# converter.net
KiCad netlist of a schematic drawn in EAGLE
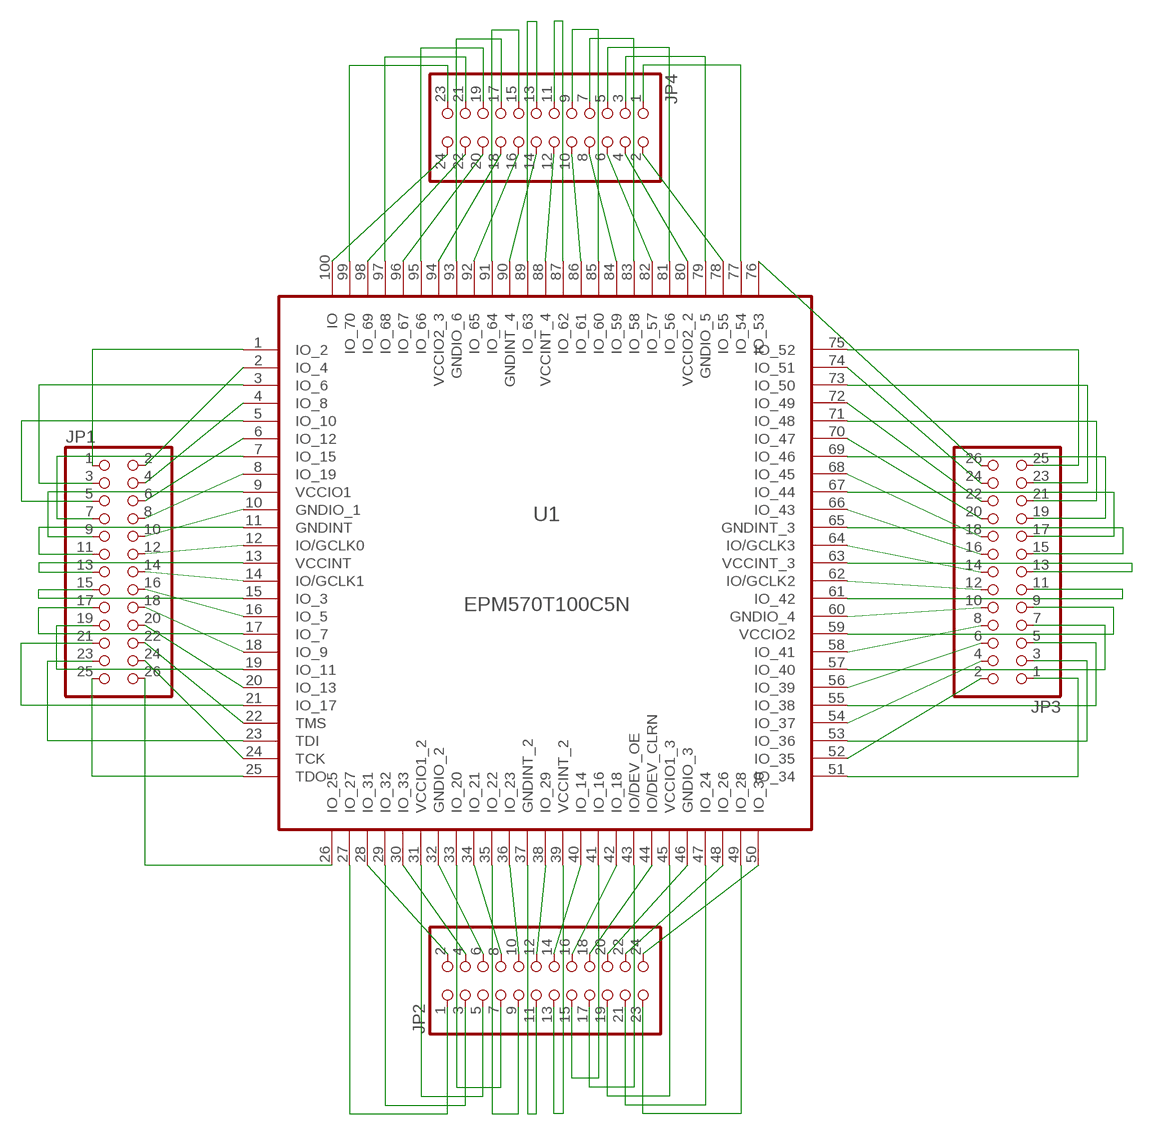
[diagram p0: schematic, sheet 1]

(export (version "E")
  (design (tool "Eeschema 10.0.6"))
  (components
    (comp (ref "JP1")
      (value "PINHD-2X13")
      (footprint "eagle-import:2X13")
      (libsource (lib "eagle-import") (part "PINHD-2X13"))
    )
    (comp (ref "JP2")
      (value "PINHD-2X12")
      (footprint "eagle-import:2X12")
      (libsource (lib "eagle-import") (part "PINHD-2X12"))
    )
    (comp (ref "JP3")
      (value "PINHD-2X13")
      (footprint "eagle-import:2X13")
      (libsource (lib "eagle-import") (part "PINHD-2X13"))
    )
    (comp (ref "JP4")
      (value "PINHD-2X12")
      (footprint "eagle-import:2X12")
      (libsource (lib "eagle-import") (part "PINHD-2X12"))
    )
    (comp (ref "U1")
      (value "EPM570T100C5N")
      (footprint "eagle-import:QFP50P1600X1600X120-100N")
      (libsource (lib "eagle-import") (part "SQUARE-QFP"))
    )
  )
  (nets
    (net (code "1") (name "Net-(U1-GNDINT)") (class "Default")
      (node (ref "JP1") (pin "11") (pinfunction "11_11") (pintype "passive"))
      (node (ref "U1") (pin "11") (pinfunction "GNDINT_11") (pintype "passive"))
    )
    (net (code "2") (name "Net-(U1-GNDINT_2)") (class "Default")
      (node (ref "JP2") (pin "11") (pinfunction "11_11") (pintype "passive"))
      (node (ref "U1") (pin "37") (pinfunction "GNDINT_2_37") (pintype "passive"))
    )
    (net (code "3") (name "Net-(U1-GNDINT_3)") (class "Default")
      (node (ref "JP3") (pin "15") (pinfunction "15_15") (pintype "passive"))
      (node (ref "U1") (pin "65") (pinfunction "GNDINT_3_65") (pintype "passive"))
    )
    (net (code "4") (name "Net-(U1-GNDINT_4)") (class "Default")
      (node (ref "JP4") (pin "14") (pinfunction "14_14") (pintype "passive"))
      (node (ref "U1") (pin "90") (pinfunction "GNDINT_4_90") (pintype "passive"))
    )
    (net (code "5") (name "Net-(U1-GNDIO_1)") (class "Default")
      (node (ref "JP1") (pin "10") (pinfunction "10_10") (pintype "passive"))
      (node (ref "U1") (pin "10") (pinfunction "GNDIO_1_10") (pintype "passive"))
    )
    (net (code "6") (name "Net-(U1-GNDIO_2)") (class "Default")
      (node (ref "JP2") (pin "6") (pinfunction "6_6") (pintype "passive"))
      (node (ref "U1") (pin "32") (pinfunction "GNDIO_2_32") (pintype "passive"))
    )
    (net (code "7") (name "Net-(U1-GNDIO_3)") (class "Default")
      (node (ref "JP2") (pin "20") (pinfunction "20_20") (pintype "passive"))
      (node (ref "U1") (pin "46") (pinfunction "GNDIO_3_46") (pintype "passive"))
    )
    (net (code "8") (name "Net-(U1-GNDIO_4)") (class "Default")
      (node (ref "JP3") (pin "10") (pinfunction "10_10") (pintype "passive"))
      (node (ref "U1") (pin "60") (pinfunction "GNDIO_4_60") (pintype "passive"))
    )
    (net (code "9") (name "Net-(U1-GNDIO_5)") (class "Default")
      (node (ref "JP4") (pin "3") (pinfunction "3_3") (pintype "passive"))
      (node (ref "U1") (pin "79") (pinfunction "GNDIO_5_79") (pintype "passive"))
    )
    (net (code "10") (name "Net-(U1-GNDIO_6)") (class "Default")
      (node (ref "JP4") (pin "17") (pinfunction "17_17") (pintype "passive"))
      (node (ref "U1") (pin "93") (pinfunction "GNDIO_6_93") (pintype "passive"))
    )
    (net (code "11") (name "Net-(U1-IO)") (class "Default")
      (node (ref "JP4") (pin "24") (pinfunction "24_24") (pintype "passive"))
      (node (ref "U1") (pin "100") (pinfunction "IO_100") (pintype "bidirectional"))
    )
    (net (code "12") (name "Net-(U1-IO_2)") (class "Default")
      (node (ref "JP1") (pin "1") (pinfunction "1_1") (pintype "passive"))
      (node (ref "U1") (pin "1") (pinfunction "IO_2_1") (pintype "bidirectional"))
    )
    (net (code "13") (name "Net-(U1-IO_3)") (class "Default")
      (node (ref "JP1") (pin "15") (pinfunction "15_15") (pintype "passive"))
      (node (ref "U1") (pin "15") (pinfunction "IO_3_15") (pintype "bidirectional"))
    )
    (net (code "14") (name "Net-(U1-IO_4)") (class "Default")
      (node (ref "JP1") (pin "2") (pinfunction "2_2") (pintype "passive"))
      (node (ref "U1") (pin "2") (pinfunction "IO_4_2") (pintype "bidirectional"))
    )
    (net (code "15") (name "Net-(U1-IO_5)") (class "Default")
      (node (ref "JP1") (pin "16") (pinfunction "16_16") (pintype "passive"))
      (node (ref "U1") (pin "16") (pinfunction "IO_5_16") (pintype "bidirectional"))
    )
    (net (code "16") (name "Net-(U1-IO_6)") (class "Default")
      (node (ref "JP1") (pin "3") (pinfunction "3_3") (pintype "passive"))
      (node (ref "U1") (pin "3") (pinfunction "IO_6_3") (pintype "bidirectional"))
    )
    (net (code "17") (name "Net-(U1-IO_7)") (class "Default")
      (node (ref "JP1") (pin "17") (pinfunction "17_17") (pintype "passive"))
      (node (ref "U1") (pin "17") (pinfunction "IO_7_17") (pintype "bidirectional"))
    )
    (net (code "18") (name "Net-(U1-IO_8)") (class "Default")
      (node (ref "JP1") (pin "4") (pinfunction "4_4") (pintype "passive"))
      (node (ref "U1") (pin "4") (pinfunction "IO_8_4") (pintype "bidirectional"))
    )
    (net (code "19") (name "Net-(U1-IO_9)") (class "Default")
      (node (ref "JP1") (pin "18") (pinfunction "18_18") (pintype "passive"))
      (node (ref "U1") (pin "18") (pinfunction "IO_9_18") (pintype "bidirectional"))
    )
    (net (code "20") (name "Net-(U1-IO_10)") (class "Default")
      (node (ref "JP1") (pin "5") (pinfunction "5_5") (pintype "passive"))
      (node (ref "U1") (pin "5") (pinfunction "IO_10_5") (pintype "bidirectional"))
    )
    (net (code "21") (name "Net-(U1-IO_11)") (class "Default")
      (node (ref "JP1") (pin "19") (pinfunction "19_19") (pintype "passive"))
      (node (ref "U1") (pin "19") (pinfunction "IO_11_19") (pintype "bidirectional"))
    )
    (net (code "22") (name "Net-(U1-IO_12)") (class "Default")
      (node (ref "JP1") (pin "6") (pinfunction "6_6") (pintype "passive"))
      (node (ref "U1") (pin "6") (pinfunction "IO_12_6") (pintype "bidirectional"))
    )
    (net (code "23") (name "Net-(U1-IO_13)") (class "Default")
      (node (ref "JP1") (pin "20") (pinfunction "20_20") (pintype "passive"))
      (node (ref "U1") (pin "20") (pinfunction "IO_13_20") (pintype "bidirectional"))
    )
    (net (code "24") (name "Net-(U1-IO_14)") (class "Default")
      (node (ref "JP2") (pin "14") (pinfunction "14_14") (pintype "passive"))
      (node (ref "U1") (pin "40") (pinfunction "IO_14_40") (pintype "bidirectional"))
    )
    (net (code "25") (name "Net-(U1-IO_15)") (class "Default")
      (node (ref "JP1") (pin "7") (pinfunction "7_7") (pintype "passive"))
      (node (ref "U1") (pin "7") (pinfunction "IO_15_7") (pintype "bidirectional"))
    )
    (net (code "26") (name "Net-(U1-IO_16)") (class "Default")
      (node (ref "JP2") (pin "15") (pinfunction "15_15") (pintype "passive"))
      (node (ref "U1") (pin "41") (pinfunction "IO_16_41") (pintype "bidirectional"))
    )
    (net (code "27") (name "Net-(U1-IO_17)") (class "Default")
      (node (ref "JP1") (pin "21") (pinfunction "21_21") (pintype "passive"))
      (node (ref "U1") (pin "21") (pinfunction "IO_17_21") (pintype "bidirectional"))
    )
    (net (code "28") (name "Net-(U1-IO_18)") (class "Default")
      (node (ref "JP2") (pin "16") (pinfunction "16_16") (pintype "passive"))
      (node (ref "U1") (pin "42") (pinfunction "IO_18_42") (pintype "bidirectional"))
    )
    (net (code "29") (name "Net-(U1-IO_19)") (class "Default")
      (node (ref "JP1") (pin "8") (pinfunction "8_8") (pintype "passive"))
      (node (ref "U1") (pin "8") (pinfunction "IO_19_8") (pintype "bidirectional"))
    )
    (net (code "30") (name "Net-(U1-IO_20)") (class "Default")
      (node (ref "JP2") (pin "7") (pinfunction "7_7") (pintype "passive"))
      (node (ref "U1") (pin "33") (pinfunction "IO_20_33") (pintype "bidirectional"))
    )
    (net (code "31") (name "Net-(U1-IO_21)") (class "Default")
      (node (ref "JP2") (pin "8") (pinfunction "8_8") (pintype "passive"))
      (node (ref "U1") (pin "34") (pinfunction "IO_21_34") (pintype "bidirectional"))
    )
    (net (code "32") (name "Net-(U1-IO_22)") (class "Default")
      (node (ref "JP2") (pin "9") (pinfunction "9_9") (pintype "passive"))
      (node (ref "U1") (pin "35") (pinfunction "IO_22_35") (pintype "bidirectional"))
    )
    (net (code "33") (name "Net-(U1-IO_23)") (class "Default")
      (node (ref "JP2") (pin "10") (pinfunction "10_10") (pintype "passive"))
      (node (ref "U1") (pin "36") (pinfunction "IO_23_36") (pintype "bidirectional"))
    )
    (net (code "34") (name "Net-(U1-IO_24)") (class "Default")
      (node (ref "JP2") (pin "21") (pinfunction "21_21") (pintype "passive"))
      (node (ref "U1") (pin "47") (pinfunction "IO_24_47") (pintype "bidirectional"))
    )
    (net (code "35") (name "Net-(U1-IO_25)") (class "Default")
      (node (ref "JP1") (pin "26") (pinfunction "26_26") (pintype "passive"))
      (node (ref "U1") (pin "26") (pinfunction "IO_25_26") (pintype "bidirectional"))
    )
    (net (code "36") (name "Net-(U1-IO_26)") (class "Default")
      (node (ref "JP2") (pin "22") (pinfunction "22_22") (pintype "passive"))
      (node (ref "U1") (pin "48") (pinfunction "IO_26_48") (pintype "bidirectional"))
    )
    (net (code "37") (name "Net-(U1-IO_27)") (class "Default")
      (node (ref "JP2") (pin "1") (pinfunction "1_1") (pintype "passive"))
      (node (ref "U1") (pin "27") (pinfunction "IO_27_27") (pintype "bidirectional"))
    )
    (net (code "38") (name "Net-(U1-IO_28)") (class "Default")
      (node (ref "JP2") (pin "23") (pinfunction "23_23") (pintype "passive"))
      (node (ref "U1") (pin "49") (pinfunction "IO_28_49") (pintype "bidirectional"))
    )
    (net (code "39") (name "Net-(U1-IO_29)") (class "Default")
      (node (ref "JP2") (pin "12") (pinfunction "12_12") (pintype "passive"))
      (node (ref "U1") (pin "38") (pinfunction "IO_29_38") (pintype "bidirectional"))
    )
    (net (code "40") (name "Net-(U1-IO_30)") (class "Default")
      (node (ref "JP2") (pin "24") (pinfunction "24_24") (pintype "passive"))
      (node (ref "U1") (pin "50") (pinfunction "IO_30_50") (pintype "bidirectional"))
    )
    (net (code "41") (name "Net-(U1-IO_31)") (class "Default")
      (node (ref "JP2") (pin "2") (pinfunction "2_2") (pintype "passive"))
      (node (ref "U1") (pin "28") (pinfunction "IO_31_28") (pintype "bidirectional"))
    )
    (net (code "42") (name "Net-(U1-IO_32)") (class "Default")
      (node (ref "JP2") (pin "3") (pinfunction "3_3") (pintype "passive"))
      (node (ref "U1") (pin "29") (pinfunction "IO_32_29") (pintype "bidirectional"))
    )
    (net (code "43") (name "Net-(U1-IO_33)") (class "Default")
      (node (ref "JP2") (pin "4") (pinfunction "4_4") (pintype "passive"))
      (node (ref "U1") (pin "30") (pinfunction "IO_33_30") (pintype "bidirectional"))
    )
    (net (code "44") (name "Net-(U1-IO_34)") (class "Default")
      (node (ref "JP3") (pin "1") (pinfunction "1_1") (pintype "passive"))
      (node (ref "U1") (pin "51") (pinfunction "IO_34_51") (pintype "bidirectional"))
    )
    (net (code "45") (name "Net-(U1-IO_35)") (class "Default")
      (node (ref "JP3") (pin "2") (pinfunction "2_2") (pintype "passive"))
      (node (ref "U1") (pin "52") (pinfunction "IO_35_52") (pintype "bidirectional"))
    )
    (net (code "46") (name "Net-(U1-IO_36)") (class "Default")
      (node (ref "JP3") (pin "3") (pinfunction "3_3") (pintype "passive"))
      (node (ref "U1") (pin "53") (pinfunction "IO_36_53") (pintype "bidirectional"))
    )
    (net (code "47") (name "Net-(U1-IO_37)") (class "Default")
      (node (ref "JP3") (pin "4") (pinfunction "4_4") (pintype "passive"))
      (node (ref "U1") (pin "54") (pinfunction "IO_37_54") (pintype "bidirectional"))
    )
    (net (code "48") (name "Net-(U1-IO_38)") (class "Default")
      (node (ref "JP3") (pin "5") (pinfunction "5_5") (pintype "passive"))
      (node (ref "U1") (pin "55") (pinfunction "IO_38_55") (pintype "bidirectional"))
    )
    (net (code "49") (name "Net-(U1-IO_39)") (class "Default")
      (node (ref "JP3") (pin "6") (pinfunction "6_6") (pintype "passive"))
      (node (ref "U1") (pin "56") (pinfunction "IO_39_56") (pintype "bidirectional"))
    )
    (net (code "50") (name "Net-(U1-IO_40)") (class "Default")
      (node (ref "JP3") (pin "7") (pinfunction "7_7") (pintype "passive"))
      (node (ref "U1") (pin "57") (pinfunction "IO_40_57") (pintype "bidirectional"))
    )
    (net (code "51") (name "Net-(U1-IO_41)") (class "Default")
      (node (ref "JP3") (pin "8") (pinfunction "8_8") (pintype "passive"))
      (node (ref "U1") (pin "58") (pinfunction "IO_41_58") (pintype "bidirectional"))
    )
    (net (code "52") (name "Net-(U1-IO_42)") (class "Default")
      (node (ref "JP3") (pin "11") (pinfunction "11_11") (pintype "passive"))
      (node (ref "U1") (pin "61") (pinfunction "IO_42_61") (pintype "bidirectional"))
    )
    (net (code "53") (name "Net-(U1-IO_43)") (class "Default")
      (node (ref "JP3") (pin "16") (pinfunction "16_16") (pintype "passive"))
      (node (ref "U1") (pin "66") (pinfunction "IO_43_66") (pintype "bidirectional"))
    )
    (net (code "54") (name "Net-(U1-IO_44)") (class "Default")
      (node (ref "JP3") (pin "17") (pinfunction "17_17") (pintype "passive"))
      (node (ref "U1") (pin "67") (pinfunction "IO_44_67") (pintype "bidirectional"))
    )
    (net (code "55") (name "Net-(U1-IO_45)") (class "Default")
      (node (ref "JP3") (pin "18") (pinfunction "18_18") (pintype "passive"))
      (node (ref "U1") (pin "68") (pinfunction "IO_45_68") (pintype "bidirectional"))
    )
    (net (code "56") (name "Net-(U1-IO_46)") (class "Default")
      (node (ref "JP3") (pin "19") (pinfunction "19_19") (pintype "passive"))
      (node (ref "U1") (pin "69") (pinfunction "IO_46_69") (pintype "bidirectional"))
    )
    (net (code "57") (name "Net-(U1-IO_47)") (class "Default")
      (node (ref "JP3") (pin "20") (pinfunction "20_20") (pintype "passive"))
      (node (ref "U1") (pin "70") (pinfunction "IO_47_70") (pintype "bidirectional"))
    )
    (net (code "58") (name "Net-(U1-IO_48)") (class "Default")
      (node (ref "JP3") (pin "21") (pinfunction "21_21") (pintype "passive"))
      (node (ref "U1") (pin "71") (pinfunction "IO_48_71") (pintype "bidirectional"))
    )
    (net (code "59") (name "Net-(U1-IO_49)") (class "Default")
      (node (ref "JP3") (pin "22") (pinfunction "22_22") (pintype "passive"))
      (node (ref "U1") (pin "72") (pinfunction "IO_49_72") (pintype "bidirectional"))
    )
    (net (code "60") (name "Net-(U1-IO_50)") (class "Default")
      (node (ref "JP3") (pin "23") (pinfunction "23_23") (pintype "passive"))
      (node (ref "U1") (pin "73") (pinfunction "IO_50_73") (pintype "bidirectional"))
    )
    (net (code "61") (name "Net-(U1-IO_51)") (class "Default")
      (node (ref "JP3") (pin "24") (pinfunction "24_24") (pintype "passive"))
      (node (ref "U1") (pin "74") (pinfunction "IO_51_74") (pintype "bidirectional"))
    )
    (net (code "62") (name "Net-(U1-IO_52)") (class "Default")
      (node (ref "JP3") (pin "25") (pinfunction "25_25") (pintype "passive"))
      (node (ref "U1") (pin "75") (pinfunction "IO_52_75") (pintype "bidirectional"))
    )
    (net (code "63") (name "Net-(U1-IO_53)") (class "Default")
      (node (ref "JP3") (pin "26") (pinfunction "26_26") (pintype "passive"))
      (node (ref "U1") (pin "76") (pinfunction "IO_53_76") (pintype "bidirectional"))
    )
    (net (code "64") (name "Net-(U1-IO_54)") (class "Default")
      (node (ref "JP4") (pin "1") (pinfunction "1_1") (pintype "passive"))
      (node (ref "U1") (pin "77") (pinfunction "IO_54_77") (pintype "bidirectional"))
    )
    (net (code "65") (name "Net-(U1-IO_55)") (class "Default")
      (node (ref "JP4") (pin "2") (pinfunction "2_2") (pintype "passive"))
      (node (ref "U1") (pin "78") (pinfunction "IO_55_78") (pintype "bidirectional"))
    )
    (net (code "66") (name "Net-(U1-IO_56)") (class "Default")
      (node (ref "JP4") (pin "5") (pinfunction "5_5") (pintype "passive"))
      (node (ref "U1") (pin "81") (pinfunction "IO_56_81") (pintype "bidirectional"))
    )
    (net (code "67") (name "Net-(U1-IO_57)") (class "Default")
      (node (ref "JP4") (pin "6") (pinfunction "6_6") (pintype "passive"))
      (node (ref "U1") (pin "82") (pinfunction "IO_57_82") (pintype "bidirectional"))
    )
    (net (code "68") (name "Net-(U1-IO_58)") (class "Default")
      (node (ref "JP4") (pin "7") (pinfunction "7_7") (pintype "passive"))
      (node (ref "U1") (pin "83") (pinfunction "IO_58_83") (pintype "bidirectional"))
    )
    (net (code "69") (name "Net-(U1-IO_59)") (class "Default")
      (node (ref "JP4") (pin "8") (pinfunction "8_8") (pintype "passive"))
      (node (ref "U1") (pin "84") (pinfunction "IO_59_84") (pintype "bidirectional"))
    )
    (net (code "70") (name "Net-(U1-IO_60)") (class "Default")
      (node (ref "JP4") (pin "9") (pinfunction "9_9") (pintype "passive"))
      (node (ref "U1") (pin "85") (pinfunction "IO_60_85") (pintype "bidirectional"))
    )
    (net (code "71") (name "Net-(U1-IO_61)") (class "Default")
      (node (ref "JP4") (pin "10") (pinfunction "10_10") (pintype "passive"))
      (node (ref "U1") (pin "86") (pinfunction "IO_61_86") (pintype "bidirectional"))
    )
    (net (code "72") (name "Net-(U1-IO_62)") (class "Default")
      (node (ref "JP4") (pin "11") (pinfunction "11_11") (pintype "passive"))
      (node (ref "U1") (pin "87") (pinfunction "IO_62_87") (pintype "bidirectional"))
    )
    (net (code "73") (name "Net-(U1-IO_63)") (class "Default")
      (node (ref "JP4") (pin "13") (pinfunction "13_13") (pintype "passive"))
      (node (ref "U1") (pin "89") (pinfunction "IO_63_89") (pintype "bidirectional"))
    )
    (net (code "74") (name "Net-(U1-IO_64)") (class "Default")
      (node (ref "JP4") (pin "15") (pinfunction "15_15") (pintype "passive"))
      (node (ref "U1") (pin "91") (pinfunction "IO_64_91") (pintype "bidirectional"))
    )
    (net (code "75") (name "Net-(U1-IO_65)") (class "Default")
      (node (ref "JP4") (pin "16") (pinfunction "16_16") (pintype "passive"))
      (node (ref "U1") (pin "92") (pinfunction "IO_65_92") (pintype "bidirectional"))
    )
    (net (code "76") (name "Net-(U1-IO_66)") (class "Default")
      (node (ref "JP4") (pin "19") (pinfunction "19_19") (pintype "passive"))
      (node (ref "U1") (pin "95") (pinfunction "IO_66_95") (pintype "bidirectional"))
    )
    (net (code "77") (name "Net-(U1-IO_67)") (class "Default")
      (node (ref "JP4") (pin "20") (pinfunction "20_20") (pintype "passive"))
      (node (ref "U1") (pin "96") (pinfunction "IO_67_96") (pintype "bidirectional"))
    )
    (net (code "78") (name "Net-(U1-IO_68)") (class "Default")
      (node (ref "JP4") (pin "21") (pinfunction "21_21") (pintype "passive"))
      (node (ref "U1") (pin "97") (pinfunction "IO_68_97") (pintype "bidirectional"))
    )
    (net (code "79") (name "Net-(U1-IO_69)") (class "Default")
      (node (ref "JP4") (pin "22") (pinfunction "22_22") (pintype "passive"))
      (node (ref "U1") (pin "98") (pinfunction "IO_69_98") (pintype "bidirectional"))
    )
    (net (code "80") (name "Net-(U1-IO_70)") (class "Default")
      (node (ref "JP4") (pin "23") (pinfunction "23_23") (pintype "passive"))
      (node (ref "U1") (pin "99") (pinfunction "IO_70_99") (pintype "bidirectional"))
    )
    (net (code "81") (name "Net-(U1-IO{slash}DEV_CLRN)") (class "Default")
      (node (ref "JP2") (pin "18") (pinfunction "18_18") (pintype "passive"))
      (node (ref "U1") (pin "44") (pinfunction "IO/DEV_CLRN_44") (pintype "bidirectional"))
    )
    (net (code "82") (name "Net-(U1-IO{slash}DEV_OE)") (class "Default")
      (node (ref "JP2") (pin "17") (pinfunction "17_17") (pintype "passive"))
      (node (ref "U1") (pin "43") (pinfunction "IO/DEV_OE_43") (pintype "bidirectional"))
    )
    (net (code "83") (name "Net-(U1-IO{slash}GCLK0)") (class "Default")
      (node (ref "JP1") (pin "12") (pinfunction "12_12") (pintype "passive"))
      (node (ref "U1") (pin "12") (pinfunction "IO/GCLK0_12") (pintype "bidirectional"))
    )
    (net (code "84") (name "Net-(U1-IO{slash}GCLK1)") (class "Default")
      (node (ref "JP1") (pin "14") (pinfunction "14_14") (pintype "passive"))
      (node (ref "U1") (pin "14") (pinfunction "IO/GCLK1_14") (pintype "bidirectional"))
    )
    (net (code "85") (name "Net-(U1-IO{slash}GCLK2)") (class "Default")
      (node (ref "JP3") (pin "12") (pinfunction "12_12") (pintype "passive"))
      (node (ref "U1") (pin "62") (pinfunction "IO/GCLK2_62") (pintype "bidirectional"))
    )
    (net (code "86") (name "Net-(U1-IO{slash}GCLK3)") (class "Default")
      (node (ref "JP3") (pin "14") (pinfunction "14_14") (pintype "passive"))
      (node (ref "U1") (pin "64") (pinfunction "IO/GCLK3_64") (pintype "bidirectional"))
    )
    (net (code "87") (name "Net-(U1-TCK)") (class "Default")
      (node (ref "JP1") (pin "24") (pinfunction "24_24") (pintype "passive"))
      (node (ref "U1") (pin "24") (pinfunction "TCK_24") (pintype "passive"))
    )
    (net (code "88") (name "Net-(U1-TDI)") (class "Default")
      (node (ref "JP1") (pin "23") (pinfunction "23_23") (pintype "passive"))
      (node (ref "U1") (pin "23") (pinfunction "TDI_23") (pintype "passive"))
    )
    (net (code "89") (name "Net-(U1-TDO)") (class "Default")
      (node (ref "JP1") (pin "25") (pinfunction "25_25") (pintype "passive"))
      (node (ref "U1") (pin "25") (pinfunction "TDO_25") (pintype "output"))
    )
    (net (code "90") (name "Net-(U1-TMS)") (class "Default")
      (node (ref "JP1") (pin "22") (pinfunction "22_22") (pintype "passive"))
      (node (ref "U1") (pin "22") (pinfunction "TMS_22") (pintype "passive"))
    )
    (net (code "91") (name "Net-(U1-VCCINT)") (class "Default")
      (node (ref "JP1") (pin "13") (pinfunction "13_13") (pintype "passive"))
      (node (ref "U1") (pin "13") (pinfunction "VCCINT_13") (pintype "power_in"))
    )
    (net (code "92") (name "Net-(U1-VCCINT_2)") (class "Default")
      (node (ref "JP2") (pin "13") (pinfunction "13_13") (pintype "passive"))
      (node (ref "U1") (pin "39") (pinfunction "VCCINT_2_39") (pintype "power_in"))
    )
    (net (code "93") (name "Net-(U1-VCCINT_3)") (class "Default")
      (node (ref "JP3") (pin "13") (pinfunction "13_13") (pintype "passive"))
      (node (ref "U1") (pin "63") (pinfunction "VCCINT_3_63") (pintype "power_in"))
    )
    (net (code "94") (name "Net-(U1-VCCINT_4)") (class "Default")
      (node (ref "JP4") (pin "12") (pinfunction "12_12") (pintype "passive"))
      (node (ref "U1") (pin "88") (pinfunction "VCCINT_4_88") (pintype "power_in"))
    )
    (net (code "95") (name "Net-(U1-VCCIO1)") (class "Default")
      (node (ref "JP1") (pin "9") (pinfunction "9_9") (pintype "passive"))
      (node (ref "U1") (pin "9") (pinfunction "VCCIO1_9") (pintype "power_in"))
    )
    (net (code "96") (name "Net-(U1-VCCIO1_2)") (class "Default")
      (node (ref "JP2") (pin "5") (pinfunction "5_5") (pintype "passive"))
      (node (ref "U1") (pin "31") (pinfunction "VCCIO1_2_31") (pintype "power_in"))
    )
    (net (code "97") (name "Net-(U1-VCCIO1_3)") (class "Default")
      (node (ref "JP2") (pin "19") (pinfunction "19_19") (pintype "passive"))
      (node (ref "U1") (pin "45") (pinfunction "VCCIO1_3_45") (pintype "power_in"))
    )
    (net (code "98") (name "Net-(U1-VCCIO2)") (class "Default")
      (node (ref "JP3") (pin "9") (pinfunction "9_9") (pintype "passive"))
      (node (ref "U1") (pin "59") (pinfunction "VCCIO2_59") (pintype "power_in"))
    )
    (net (code "99") (name "Net-(U1-VCCIO2_2)") (class "Default")
      (node (ref "JP4") (pin "4") (pinfunction "4_4") (pintype "passive"))
      (node (ref "U1") (pin "80") (pinfunction "VCCIO2_2_80") (pintype "power_in"))
    )
    (net (code "100") (name "Net-(U1-VCCIO2_3)") (class "Default")
      (node (ref "JP4") (pin "18") (pinfunction "18_18") (pintype "passive"))
      (node (ref "U1") (pin "94") (pinfunction "VCCIO2_3_94") (pintype "power_in"))
    )
  )
)
